# ports.net
KiCad netlist of a schematic drawn in Altium Designer
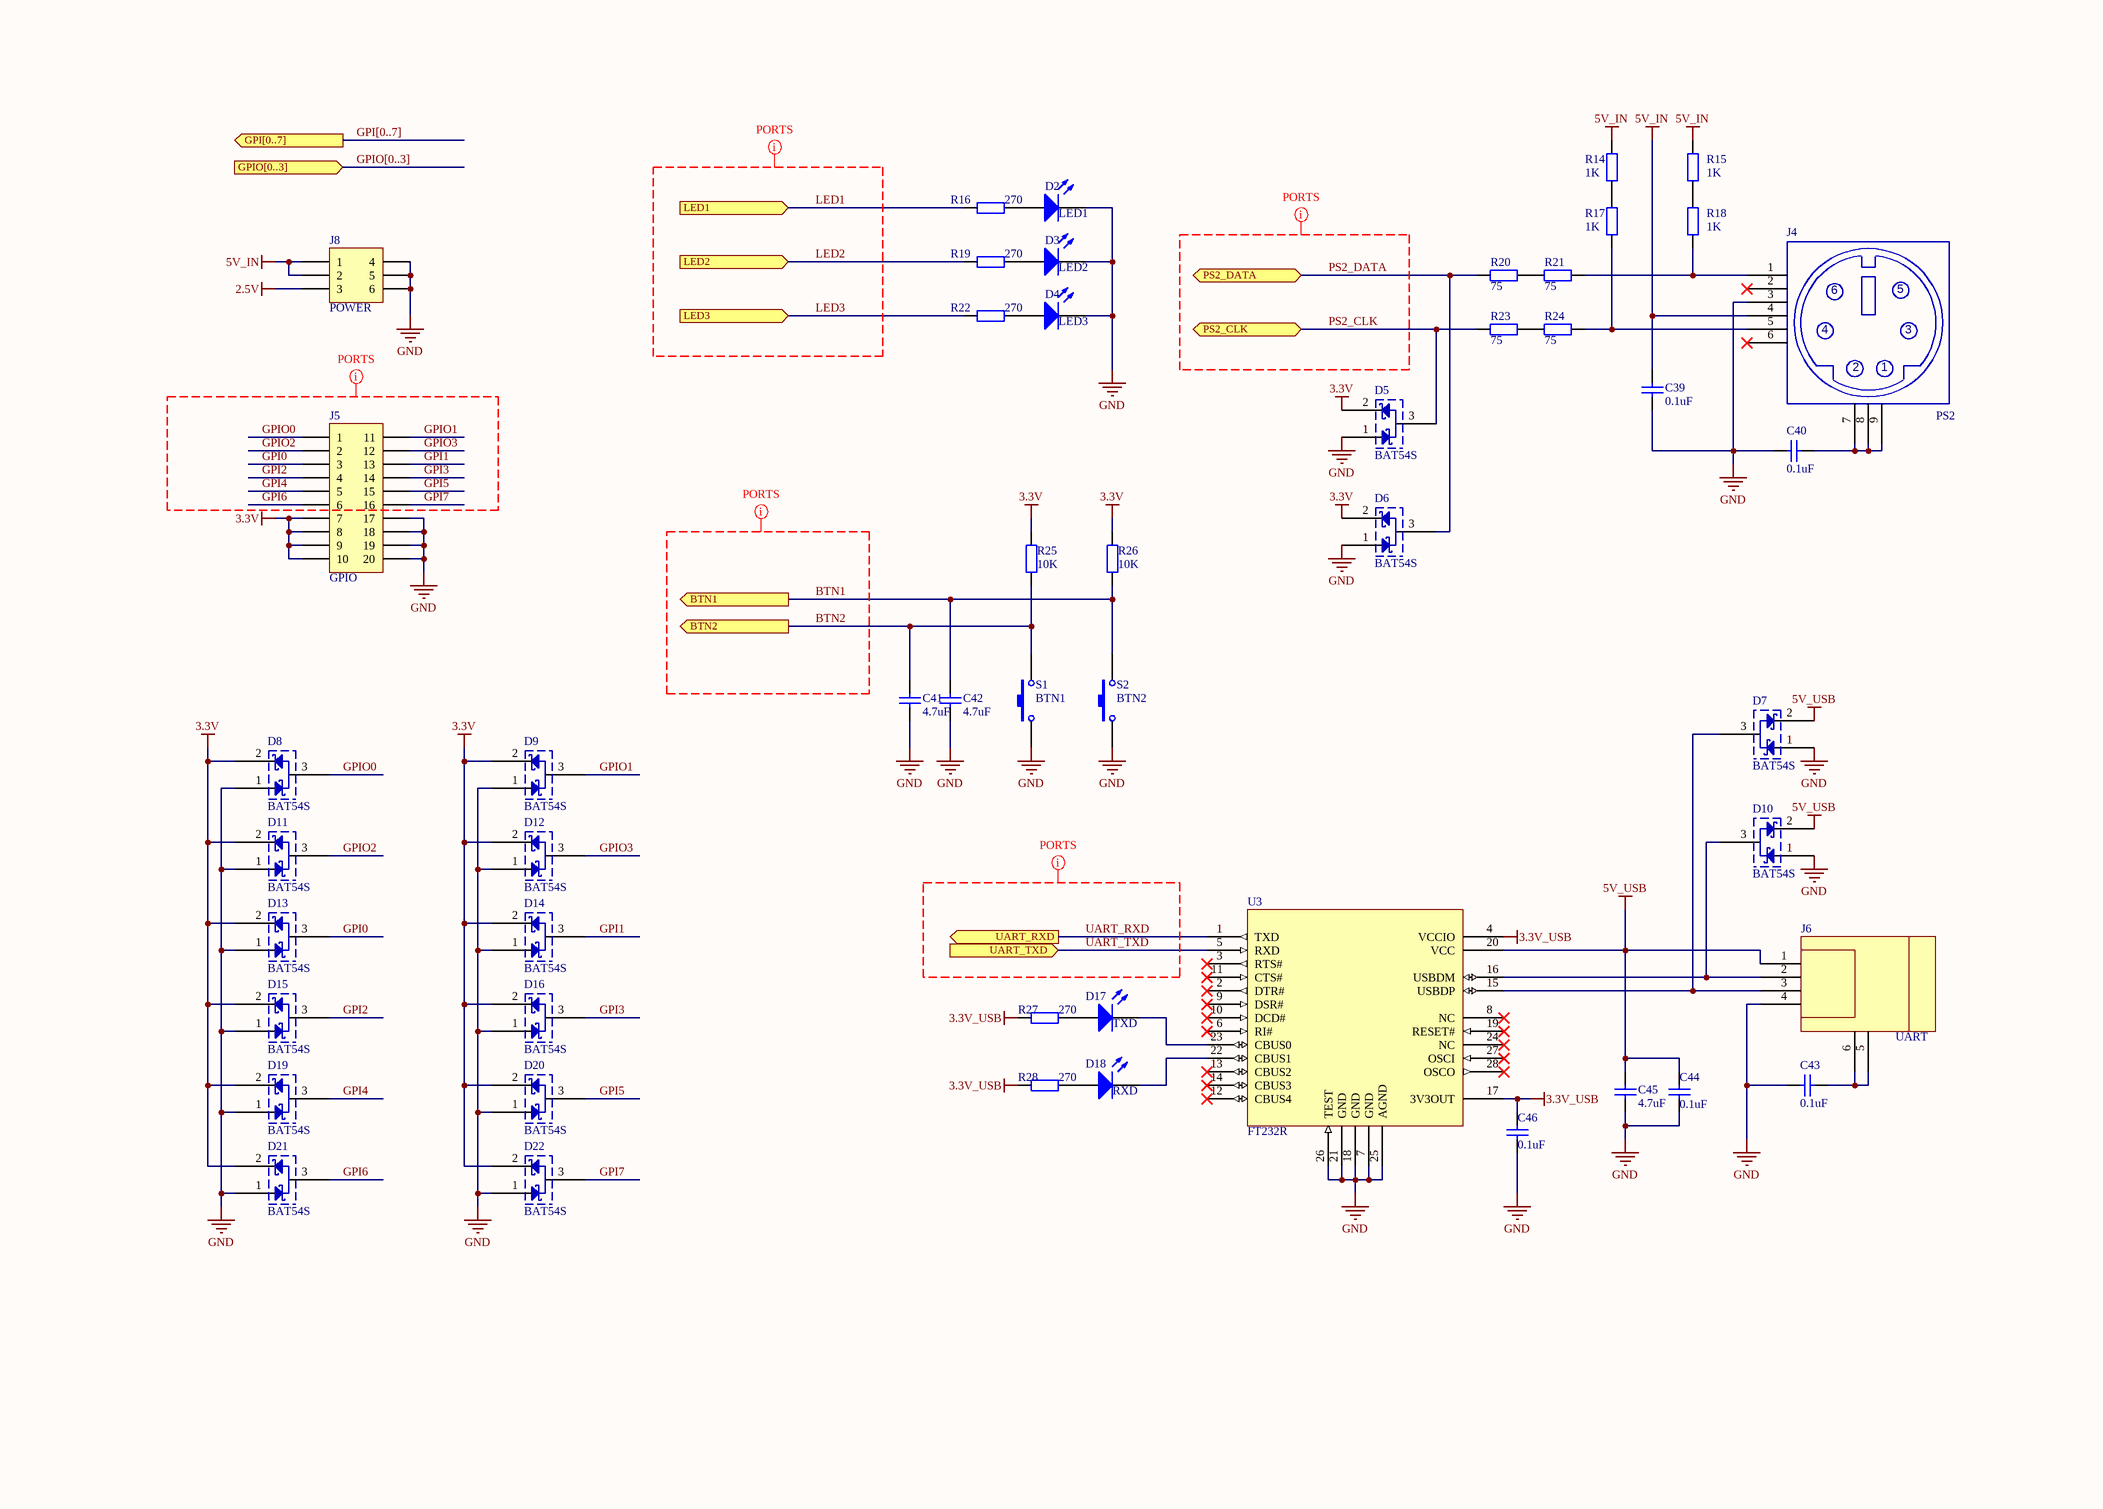
[diagram p0: ports.SchDoc]

(export (version "E")
  (design (tool "Eeschema 10.0.6"))
  (components
    (comp (ref "C39")
      (value "0.1uF")
      (footprint "0402")
      (description "Capacitor")
      (fields (field (name "Comment") "Cap") (field (name "PUBLISHER") "Altium Limited"))
      (libsource (lib "Miscellaneous Devices") (part "Cap"))
    )
    (comp (ref "C40")
      (value "0.1uF")
      (footprint "0402")
      (description "Capacitor")
      (fields (field (name "Comment") "Cap") (field (name "PUBLISHER") "Altium Limited"))
      (libsource (lib "Miscellaneous Devices") (part "Cap"))
    )
    (comp (ref "C41")
      (value "4.7uF")
      (footprint "C0805")
      (description "Capacitor")
      (fields (field (name "Comment") "Cap") (field (name "PUBLISHER") "Altium Limited"))
      (libsource (lib "Miscellaneous Devices") (part "Cap"))
    )
    (comp (ref "C42")
      (value "4.7uF")
      (footprint "C0805")
      (description "Capacitor")
      (fields (field (name "Comment") "Cap") (field (name "PUBLISHER") "Altium Limited"))
      (libsource (lib "Miscellaneous Devices") (part "Cap"))
    )
    (comp (ref "C43")
      (value "0.1uF")
      (footprint "0402")
      (description "Capacitor")
      (fields (field (name "Comment") "Cap") (field (name "PUBLISHER") "Altium Limited"))
      (libsource (lib "Miscellaneous Devices") (part "Cap"))
    )
    (comp (ref "C44")
      (value "0.1uF")
      (footprint "0402")
      (description "Capacitor")
      (fields (field (name "Comment") "Cap") (field (name "PUBLISHER") "Altium Limited"))
      (libsource (lib "Miscellaneous Devices") (part "Cap"))
    )
    (comp (ref "C45")
      (value "4.7uF")
      (footprint "C0805")
      (description "Capacitor")
      (fields (field (name "Comment") "Cap") (field (name "PUBLISHER") "Altium Limited"))
      (libsource (lib "Miscellaneous Devices") (part "Cap"))
    )
    (comp (ref "C46")
      (value "0.1uF")
      (footprint "0402")
      (description "Capacitor")
      (fields (field (name "Comment") "Cap") (field (name "PUBLISHER") "Altium Limited"))
      (libsource (lib "Miscellaneous Devices") (part "Cap"))
    )
    (comp (ref "D2")
      (value "LED1")
      (footprint "LED")
      (description "Amber")
      (fields (field (name "PUBLISHER") "Altium Limited"))
      (libsource (lib "Miscellaneous Devices") (part "LED3"))
    )
    (comp (ref "D3")
      (value "LED2")
      (footprint "LED")
      (description "Amber")
      (fields (field (name "PUBLISHER") "Altium Limited"))
      (libsource (lib "Miscellaneous Devices") (part "LED3"))
    )
    (comp (ref "D4")
      (value "LED3")
      (footprint "LED")
      (description "Amber")
      (fields (field (name "PUBLISHER") "Altium Limited"))
      (libsource (lib "Miscellaneous Devices") (part "LED3"))
    )
    (comp (ref "D5")
      (value "BAT54S")
      (footprint "SOT23_BAT54S")
      (libsource (lib "FPGA_board") (part "BAT54S"))
    )
    (comp (ref "D6")
      (value "BAT54S")
      (footprint "SOT23_BAT54S")
      (libsource (lib "FPGA_board") (part "BAT54S"))
    )
    (comp (ref "D7")
      (value "BAT54S")
      (footprint "SOT23_BAT54S")
      (libsource (lib "FPGA_board") (part "BAT54S"))
    )
    (comp (ref "D8")
      (value "BAT54S")
      (footprint "SOT23_BAT54S")
      (libsource (lib "FPGA_board") (part "BAT54S"))
    )
    (comp (ref "D9")
      (value "BAT54S")
      (footprint "SOT23_BAT54S")
      (libsource (lib "FPGA_board") (part "BAT54S"))
    )
    (comp (ref "D10")
      (value "BAT54S")
      (footprint "SOT23_BAT54S")
      (libsource (lib "FPGA_board") (part "BAT54S"))
    )
    (comp (ref "D11")
      (value "BAT54S")
      (footprint "SOT23_BAT54S")
      (libsource (lib "FPGA_board") (part "BAT54S"))
    )
    (comp (ref "D12")
      (value "BAT54S")
      (footprint "SOT23_BAT54S")
      (libsource (lib "FPGA_board") (part "BAT54S"))
    )
    (comp (ref "D13")
      (value "BAT54S")
      (footprint "SOT23_BAT54S")
      (libsource (lib "FPGA_board") (part "BAT54S"))
    )
    (comp (ref "D14")
      (value "BAT54S")
      (footprint "SOT23_BAT54S")
      (libsource (lib "FPGA_board") (part "BAT54S"))
    )
    (comp (ref "D15")
      (value "BAT54S")
      (footprint "SOT23_BAT54S")
      (libsource (lib "FPGA_board") (part "BAT54S"))
    )
    (comp (ref "D16")
      (value "BAT54S")
      (footprint "SOT23_BAT54S")
      (libsource (lib "FPGA_board") (part "BAT54S"))
    )
    (comp (ref "D17")
      (value "TXD")
      (footprint "LED")
      (description "Green")
      (fields (field (name "PUBLISHER") "Altium Limited"))
      (libsource (lib "Miscellaneous Devices") (part "LED3"))
    )
    (comp (ref "D18")
      (value "RXD")
      (footprint "LED")
      (description "Red")
      (fields (field (name "PUBLISHER") "Altium Limited"))
      (libsource (lib "Miscellaneous Devices") (part "LED3"))
    )
    (comp (ref "D19")
      (value "BAT54S")
      (footprint "SOT23_BAT54S")
      (libsource (lib "FPGA_board") (part "BAT54S"))
    )
    (comp (ref "D20")
      (value "BAT54S")
      (footprint "SOT23_BAT54S")
      (libsource (lib "FPGA_board") (part "BAT54S"))
    )
    (comp (ref "D21")
      (value "BAT54S")
      (footprint "SOT23_BAT54S")
      (libsource (lib "FPGA_board") (part "BAT54S"))
    )
    (comp (ref "D22")
      (value "BAT54S")
      (footprint "SOT23_BAT54S")
      (libsource (lib "FPGA_board") (part "BAT54S"))
    )
    (comp (ref "J4") (value "PS2") (footprint "PS2-6PIN") (libsource (lib "FPGA_board") (part "PS2_Socket")))
    (comp (ref "J5")
      (value "GPIO")
      (footprint "HDR2X10_CEN")
      (description "Header, 10-Pin, Dual row")
      (fields (field (name "PUBLISHER") "Altium Limited"))
      (libsource (lib "Miscellaneous Connectors") (part "Header 10X2A"))
    )
    (comp (ref "J6") (value "UART") (footprint "USB_B") (libsource (lib "FPGA_board") (part "USB_B")))
    (comp (ref "J8")
      (value "POWER")
      (footprint "HDR2X3_CEN")
      (description "Header, 3-Pin, Dual row")
      (fields (field (name "PUBLISHER") "Altium Limited"))
      (libsource (lib "Miscellaneous Connectors") (part "Header 3X2A"))
    )
    (comp (ref "R14")
      (value "1K")
      (footprint "J1-0603")
      (description "Resistor")
      (fields (field (name "Comment") "Res2") (field (name "PUBLISHER") "Altium Limited"))
      (libsource (lib "Miscellaneous Devices") (part "Res2"))
    )
    (comp (ref "R15")
      (value "1K")
      (footprint "J1-0603")
      (description "Resistor")
      (fields (field (name "Comment") "Res2") (field (name "PUBLISHER") "Altium Limited"))
      (libsource (lib "Miscellaneous Devices") (part "Res2"))
    )
    (comp (ref "R16")
      (value "270")
      (footprint "6-0805_N")
      (description "Resistor")
      (fields (field (name "Comment") "Res2") (field (name "PUBLISHER") "Altium Limited"))
      (libsource (lib "") (part "Res2_1"))
    )
    (comp (ref "R17")
      (value "1K")
      (footprint "J1-0603")
      (description "Resistor")
      (fields (field (name "Comment") "Res2") (field (name "PUBLISHER") "Altium Limited"))
      (libsource (lib "Miscellaneous Devices") (part "Res2"))
    )
    (comp (ref "R18")
      (value "1K")
      (footprint "J1-0603")
      (description "Resistor")
      (fields (field (name "Comment") "Res2") (field (name "PUBLISHER") "Altium Limited"))
      (libsource (lib "Miscellaneous Devices") (part "Res2"))
    )
    (comp (ref "R19")
      (value "270")
      (footprint "6-0805_N")
      (description "Resistor")
      (fields (field (name "Comment") "Res2") (field (name "PUBLISHER") "Altium Limited"))
      (libsource (lib "") (part "Res2_1"))
    )
    (comp (ref "R20")
      (value "75")
      (footprint "J1-0603")
      (description "Resistor")
      (fields (field (name "Comment") "Res2") (field (name "PUBLISHER") "Altium Limited"))
      (libsource (lib "") (part "Res2_2"))
    )
    (comp (ref "R21")
      (value "75")
      (footprint "J1-0603")
      (description "Resistor")
      (fields (field (name "Comment") "Res2") (field (name "PUBLISHER") "Altium Limited"))
      (libsource (lib "") (part "Res2_2"))
    )
    (comp (ref "R22")
      (value "270")
      (footprint "6-0805_N")
      (description "Resistor")
      (fields (field (name "Comment") "Res2") (field (name "PUBLISHER") "Altium Limited"))
      (libsource (lib "") (part "Res2_1"))
    )
    (comp (ref "R23")
      (value "75")
      (footprint "J1-0603")
      (description "Resistor")
      (fields (field (name "Comment") "Res2") (field (name "PUBLISHER") "Altium Limited"))
      (libsource (lib "") (part "Res2_2"))
    )
    (comp (ref "R24")
      (value "75")
      (footprint "J1-0603")
      (description "Resistor")
      (fields (field (name "Comment") "Res2") (field (name "PUBLISHER") "Altium Limited"))
      (libsource (lib "") (part "Res2_2"))
    )
    (comp (ref "R25")
      (value "10K")
      (footprint "J1-0603")
      (description "Resistor")
      (fields (field (name "Comment") "Res2") (field (name "PUBLISHER") "Altium Limited"))
      (libsource (lib "") (part "Res2_3"))
    )
    (comp (ref "R26")
      (value "10K")
      (footprint "J1-0603")
      (description "Resistor")
      (fields (field (name "Comment") "Res2") (field (name "PUBLISHER") "Altium Limited"))
      (libsource (lib "") (part "Res2_3"))
    )
    (comp (ref "R27")
      (value "270")
      (footprint "6-0805_N")
      (description "Resistor")
      (fields (field (name "Comment") "Res2") (field (name "PUBLISHER") "Altium Limited"))
      (libsource (lib "") (part "Res2_1"))
    )
    (comp (ref "R28")
      (value "270")
      (footprint "6-0805_N")
      (description "Resistor")
      (fields (field (name "Comment") "Res2") (field (name "PUBLISHER") "Altium Limited"))
      (libsource (lib "") (part "Res2_1"))
    )
    (comp (ref "S1")
      (value "BTN1")
      (footprint "PUSHBUTTON")
      (description "Switch")
      (fields (field (name "PUBLISHER") "Altium Limited"))
      (libsource (lib "Miscellaneous Devices") (part "SW-PB"))
    )
    (comp (ref "S2")
      (value "BTN2")
      (footprint "PUSHBUTTON")
      (description "Switch")
      (fields (field (name "PUBLISHER") "Altium Limited"))
      (libsource (lib "Miscellaneous Devices") (part "SW-PB"))
    )
    (comp (ref "U3") (value "FT232R") (footprint "SSOP28") (libsource (lib "FPGA_board") (part "FT232R")))
  )
  (nets
    (net (code "1") (name "/BTN1") (class "Default")
      (node (ref "C42") (pin "2") (pinfunction "2_2") (pintype "passive"))
      (node (ref "R26") (pin "2") (pinfunction "2_2") (pintype "passive"))
      (node (ref "S2") (pin "2") (pinfunction "2_2") (pintype "passive"))
    )
    (net (code "2") (name "/BTN2") (class "Default")
      (node (ref "C41") (pin "2") (pinfunction "2_2") (pintype "passive"))
      (node (ref "R25") (pin "2") (pinfunction "2_2") (pintype "passive"))
      (node (ref "S1") (pin "2") (pinfunction "2_2") (pintype "passive"))
    )
    (net (code "3") (name "/GPI0") (class "Default")
      (node (ref "D13") (pin "3") (pinfunction "3_3") (pintype "passive"))
      (node (ref "J5") (pin "3") (pinfunction "3_3") (pintype "passive"))
    )
    (net (code "4") (name "/GPI1") (class "Default")
      (node (ref "D14") (pin "3") (pinfunction "3_3") (pintype "passive"))
      (node (ref "J5") (pin "13") (pinfunction "13_13") (pintype "passive"))
    )
    (net (code "5") (name "/GPI2") (class "Default")
      (node (ref "D15") (pin "3") (pinfunction "3_3") (pintype "passive"))
      (node (ref "J5") (pin "4") (pinfunction "4_4") (pintype "passive"))
    )
    (net (code "6") (name "/GPI3") (class "Default")
      (node (ref "D16") (pin "3") (pinfunction "3_3") (pintype "passive"))
      (node (ref "J5") (pin "14") (pinfunction "14_14") (pintype "passive"))
    )
    (net (code "7") (name "/GPI4") (class "Default")
      (node (ref "D19") (pin "3") (pinfunction "3_3") (pintype "passive"))
      (node (ref "J5") (pin "5") (pinfunction "5_5") (pintype "passive"))
    )
    (net (code "8") (name "/GPI5") (class "Default")
      (node (ref "D20") (pin "3") (pinfunction "3_3") (pintype "passive"))
      (node (ref "J5") (pin "15") (pinfunction "15_15") (pintype "passive"))
    )
    (net (code "9") (name "/GPI6") (class "Default")
      (node (ref "D21") (pin "3") (pinfunction "3_3") (pintype "passive"))
      (node (ref "J5") (pin "6") (pinfunction "6_6") (pintype "passive"))
    )
    (net (code "10") (name "/GPI7") (class "Default")
      (node (ref "D22") (pin "3") (pinfunction "3_3") (pintype "passive"))
      (node (ref "J5") (pin "16") (pinfunction "16_16") (pintype "passive"))
    )
    (net (code "11") (name "/GPIO0") (class "Default")
      (node (ref "D8") (pin "3") (pinfunction "3_3") (pintype "passive"))
      (node (ref "J5") (pin "1") (pinfunction "1_1") (pintype "passive"))
    )
    (net (code "12") (name "/GPIO1") (class "Default")
      (node (ref "D9") (pin "3") (pinfunction "3_3") (pintype "passive"))
      (node (ref "J5") (pin "11") (pinfunction "11_11") (pintype "passive"))
    )
    (net (code "13") (name "/GPIO2") (class "Default")
      (node (ref "D11") (pin "3") (pinfunction "3_3") (pintype "passive"))
      (node (ref "J5") (pin "2") (pinfunction "2_2") (pintype "passive"))
    )
    (net (code "14") (name "/GPIO3") (class "Default")
      (node (ref "D12") (pin "3") (pinfunction "3_3") (pintype "passive"))
      (node (ref "J5") (pin "12") (pinfunction "12_12") (pintype "passive"))
    )
    (net (code "17") (name "/LED1") (class "Default")
      (node (ref "R16") (pin "2") (pinfunction "2_2") (pintype "passive"))
    )
    (net (code "18") (name "/LED2") (class "Default")
      (node (ref "R19") (pin "2") (pinfunction "2_2") (pintype "passive"))
    )
    (net (code "19") (name "/LED3") (class "Default")
      (node (ref "R22") (pin "2") (pinfunction "2_2") (pintype "passive"))
    )
    (net (code "20") (name "/PS2_CLK") (class "Default")
      (node (ref "D5") (pin "3") (pinfunction "3_3") (pintype "passive"))
      (node (ref "R23") (pin "1") (pinfunction "1_1") (pintype "passive"))
    )
    (net (code "21") (name "/PS2_DATA") (class "Default")
      (node (ref "D6") (pin "3") (pinfunction "3_3") (pintype "passive"))
      (node (ref "R20") (pin "1") (pinfunction "1_1") (pintype "passive"))
    )
    (net (code "22") (name "/UART_RXD") (class "Default")
      (node (ref "U3") (pin "1") (pinfunction "TXD_1") (pintype "output"))
    )
    (net (code "23") (name "/UART_TXD") (class "Default")
      (node (ref "U3") (pin "5") (pinfunction "RXD_5") (pintype "input"))
    )
    (net (code "24") (name "2.5V") (class "Default")
      (node (ref "J8") (pin "3") (pinfunction "3_3") (pintype "passive"))
    )
    (net (code "25") (name "3.3V") (class "Default")
      (node (ref "D11") (pin "2") (pinfunction "2_2") (pintype "passive"))
      (node (ref "D12") (pin "2") (pinfunction "2_2") (pintype "passive"))
      (node (ref "D13") (pin "2") (pinfunction "2_2") (pintype "passive"))
      (node (ref "D14") (pin "2") (pinfunction "2_2") (pintype "passive"))
      (node (ref "D15") (pin "2") (pinfunction "2_2") (pintype "passive"))
      (node (ref "D16") (pin "2") (pinfunction "2_2") (pintype "passive"))
      (node (ref "D19") (pin "2") (pinfunction "2_2") (pintype "passive"))
      (node (ref "D20") (pin "2") (pinfunction "2_2") (pintype "passive"))
      (node (ref "D21") (pin "2") (pinfunction "2_2") (pintype "passive"))
      (node (ref "D22") (pin "2") (pinfunction "2_2") (pintype "passive"))
      (node (ref "D5") (pin "2") (pinfunction "2_2") (pintype "passive"))
      (node (ref "D6") (pin "2") (pinfunction "2_2") (pintype "passive"))
      (node (ref "D8") (pin "2") (pinfunction "2_2") (pintype "passive"))
      (node (ref "D9") (pin "2") (pinfunction "2_2") (pintype "passive"))
      (node (ref "J5") (pin "10") (pinfunction "10_10") (pintype "passive"))
      (node (ref "J5") (pin "7") (pinfunction "7_7") (pintype "passive"))
      (node (ref "J5") (pin "8") (pinfunction "8_8") (pintype "passive"))
      (node (ref "J5") (pin "9") (pinfunction "9_9") (pintype "passive"))
      (node (ref "R25") (pin "1") (pinfunction "1_1") (pintype "passive"))
      (node (ref "R26") (pin "1") (pinfunction "1_1") (pintype "passive"))
    )
    (net (code "26") (name "3.3V_USB") (class "Default")
      (node (ref "C46") (pin "1") (pinfunction "1_1") (pintype "passive"))
      (node (ref "R27") (pin "2") (pinfunction "2_2") (pintype "passive"))
      (node (ref "R28") (pin "2") (pinfunction "2_2") (pintype "passive"))
      (node (ref "U3") (pin "17") (pinfunction "3V3OUT_17") (pintype "power_in"))
      (node (ref "U3") (pin "4") (pinfunction "VCCIO_4") (pintype "power_in"))
    )
    (net (code "27") (name "5V_IN") (class "Default")
      (node (ref "C39") (pin "2") (pinfunction "2_2") (pintype "passive"))
      (node (ref "J4") (pin "4") (pintype "passive"))
      (node (ref "J8") (pin "1") (pinfunction "1_1") (pintype "passive"))
      (node (ref "J8") (pin "2") (pinfunction "2_2") (pintype "passive"))
      (node (ref "R14") (pin "2") (pinfunction "2_2") (pintype "passive"))
      (node (ref "R15") (pin "2") (pinfunction "2_2") (pintype "passive"))
    )
    (net (code "28") (name "5V_USB") (class "Default")
      (node (ref "C44") (pin "1") (pinfunction "1_1") (pintype "passive"))
      (node (ref "C45") (pin "2") (pinfunction "2_2") (pintype "passive"))
      (node (ref "D10") (pin "2") (pinfunction "2_2") (pintype "passive"))
      (node (ref "D7") (pin "2") (pinfunction "2_2") (pintype "passive"))
      (node (ref "J6") (pin "1") (pintype "passive"))
      (node (ref "U3") (pin "20") (pinfunction "VCC_20") (pintype "power_in"))
    )
    (net (code "29") (name "GND") (class "Default")
      (node (ref "C39") (pin "1") (pinfunction "1_1") (pintype "passive"))
      (node (ref "C40") (pin "1") (pinfunction "1_1") (pintype "passive"))
      (node (ref "C41") (pin "1") (pinfunction "1_1") (pintype "passive"))
      (node (ref "C42") (pin "1") (pinfunction "1_1") (pintype "passive"))
      (node (ref "C43") (pin "1") (pinfunction "1_1") (pintype "passive"))
      (node (ref "C44") (pin "2") (pinfunction "2_2") (pintype "passive"))
      (node (ref "C45") (pin "1") (pinfunction "1_1") (pintype "passive"))
      (node (ref "C46") (pin "2") (pinfunction "2_2") (pintype "passive"))
      (node (ref "D10") (pin "1") (pinfunction "1_1") (pintype "passive"))
      (node (ref "D11") (pin "1") (pinfunction "1_1") (pintype "passive"))
      (node (ref "D12") (pin "1") (pinfunction "1_1") (pintype "passive"))
      (node (ref "D13") (pin "1") (pinfunction "1_1") (pintype "passive"))
      (node (ref "D14") (pin "1") (pinfunction "1_1") (pintype "passive"))
      (node (ref "D15") (pin "1") (pinfunction "1_1") (pintype "passive"))
      (node (ref "D16") (pin "1") (pinfunction "1_1") (pintype "passive"))
      (node (ref "D19") (pin "1") (pinfunction "1_1") (pintype "passive"))
      (node (ref "D2") (pin "2") (pinfunction "K_2") (pintype "passive"))
      (node (ref "D20") (pin "1") (pinfunction "1_1") (pintype "passive"))
      (node (ref "D21") (pin "1") (pinfunction "1_1") (pintype "passive"))
      (node (ref "D22") (pin "1") (pinfunction "1_1") (pintype "passive"))
      (node (ref "D3") (pin "2") (pinfunction "K_2") (pintype "passive"))
      (node (ref "D4") (pin "2") (pinfunction "K_2") (pintype "passive"))
      (node (ref "D5") (pin "1") (pinfunction "1_1") (pintype "passive"))
      (node (ref "D6") (pin "1") (pinfunction "1_1") (pintype "passive"))
      (node (ref "D7") (pin "1") (pinfunction "1_1") (pintype "passive"))
      (node (ref "D8") (pin "1") (pinfunction "1_1") (pintype "passive"))
      (node (ref "D9") (pin "1") (pinfunction "1_1") (pintype "passive"))
      (node (ref "J4") (pin "3") (pintype "passive"))
      (node (ref "J5") (pin "17") (pinfunction "17_17") (pintype "passive"))
      (node (ref "J5") (pin "18") (pinfunction "18_18") (pintype "passive"))
      (node (ref "J5") (pin "19") (pinfunction "19_19") (pintype "passive"))
      (node (ref "J5") (pin "20") (pinfunction "20_20") (pintype "passive"))
      (node (ref "J6") (pin "4") (pintype "passive"))
      (node (ref "J8") (pin "4") (pinfunction "4_4") (pintype "passive"))
      (node (ref "J8") (pin "5") (pinfunction "5_5") (pintype "passive"))
      (node (ref "J8") (pin "6") (pinfunction "6_6") (pintype "passive"))
      (node (ref "S1") (pin "1") (pinfunction "1_1") (pintype "passive"))
      (node (ref "S2") (pin "1") (pinfunction "1_1") (pintype "passive"))
      (node (ref "U3") (pin "18") (pinfunction "GND_18") (pintype "power_in"))
      (node (ref "U3") (pin "21") (pinfunction "GND_21") (pintype "power_in"))
      (node (ref "U3") (pin "25") (pinfunction "AGND_25") (pintype "power_in"))
      (node (ref "U3") (pin "26") (pinfunction "TEST_26") (pintype "input"))
      (node (ref "U3") (pin "7") (pinfunction "GND_7") (pintype "power_in"))
    )
    (net (code "30") (name "Net-(C40-Pad2)") (class "Default")
      (node (ref "C40") (pin "2") (pinfunction "2_2") (pintype "passive"))
      (node (ref "J4") (pin "7") (pintype "passive"))
      (node (ref "J4") (pin "8") (pintype "passive"))
      (node (ref "J4") (pin "9") (pintype "passive"))
    )
    (net (code "31") (name "Net-(C43-Pad2)") (class "Default")
      (node (ref "C43") (pin "2") (pinfunction "2_2") (pintype "passive"))
      (node (ref "J6") (pin "5") (pintype "passive"))
      (node (ref "J6") (pin "6") (pintype "passive"))
    )
    (net (code "32") (name "Net-(D2-A)") (class "Default")
      (node (ref "D2") (pin "1") (pinfunction "A_1") (pintype "passive"))
      (node (ref "R16") (pin "1") (pinfunction "1_1") (pintype "passive"))
    )
    (net (code "33") (name "Net-(D3-A)") (class "Default")
      (node (ref "D3") (pin "1") (pinfunction "A_1") (pintype "passive"))
      (node (ref "R19") (pin "1") (pinfunction "1_1") (pintype "passive"))
    )
    (net (code "34") (name "Net-(D4-A)") (class "Default")
      (node (ref "D4") (pin "1") (pinfunction "A_1") (pintype "passive"))
      (node (ref "R22") (pin "1") (pinfunction "1_1") (pintype "passive"))
    )
    (net (code "35") (name "Net-(D17-A)") (class "Default")
      (node (ref "D17") (pin "1") (pinfunction "A_1") (pintype "passive"))
      (node (ref "R27") (pin "1") (pinfunction "1_1") (pintype "passive"))
    )
    (net (code "36") (name "Net-(D17-K)") (class "Default")
      (node (ref "D17") (pin "2") (pinfunction "K_2") (pintype "passive"))
      (node (ref "U3") (pin "23") (pinfunction "CBUS0_23") (pintype "bidirectional"))
    )
    (net (code "37") (name "Net-(D18-A)") (class "Default")
      (node (ref "D18") (pin "1") (pinfunction "A_1") (pintype "passive"))
      (node (ref "R28") (pin "1") (pinfunction "1_1") (pintype "passive"))
    )
    (net (code "38") (name "Net-(D18-K)") (class "Default")
      (node (ref "D18") (pin "2") (pinfunction "K_2") (pintype "passive"))
      (node (ref "U3") (pin "22") (pinfunction "CBUS1_22") (pintype "bidirectional"))
    )
    (net (code "39") (name "Net-(J4-Pad1)") (class "Default")
      (node (ref "J4") (pin "1") (pintype "passive"))
      (node (ref "R18") (pin "1") (pinfunction "1_1") (pintype "passive"))
      (node (ref "R21") (pin "2") (pinfunction "2_2") (pintype "passive"))
    )
    (net (code "40") (name "Net-(J4-Pad5)") (class "Default")
      (node (ref "J4") (pin "5") (pintype "passive"))
      (node (ref "R17") (pin "1") (pinfunction "1_1") (pintype "passive"))
      (node (ref "R24") (pin "2") (pinfunction "2_2") (pintype "passive"))
    )
    (net (code "41") (name "Net-(R14-Pad1)") (class "Default")
      (node (ref "R14") (pin "1") (pinfunction "1_1") (pintype "passive"))
      (node (ref "R17") (pin "2") (pinfunction "2_2") (pintype "passive"))
    )
    (net (code "42") (name "Net-(R15-Pad1)") (class "Default")
      (node (ref "R15") (pin "1") (pinfunction "1_1") (pintype "passive"))
      (node (ref "R18") (pin "2") (pinfunction "2_2") (pintype "passive"))
    )
    (net (code "43") (name "Net-(R20-Pad2)") (class "Default")
      (node (ref "R20") (pin "2") (pinfunction "2_2") (pintype "passive"))
      (node (ref "R21") (pin "1") (pinfunction "1_1") (pintype "passive"))
    )
    (net (code "44") (name "Net-(R23-Pad2)") (class "Default")
      (node (ref "R23") (pin "2") (pinfunction "2_2") (pintype "passive"))
      (node (ref "R24") (pin "1") (pinfunction "1_1") (pintype "passive"))
    )
    (net (code "45") (name "Net-(U3-USBDM)") (class "Default")
      (node (ref "D10") (pin "3") (pinfunction "3_3") (pintype "passive"))
      (node (ref "J6") (pin "2") (pintype "passive"))
      (node (ref "U3") (pin "16") (pinfunction "USBDM_16") (pintype "bidirectional"))
    )
    (net (code "46") (name "Net-(U3-USBDP)") (class "Default")
      (node (ref "D7") (pin "3") (pinfunction "3_3") (pintype "passive"))
      (node (ref "J6") (pin "3") (pintype "passive"))
      (node (ref "U3") (pin "15") (pinfunction "USBDP_15") (pintype "bidirectional"))
    )
    (net (code "47") (name "unconnected-(J4-Pad2)") (class "Default")
      (node (ref "J4") (pin "2") (pintype "passive+no_connect"))
    )
    (net (code "48") (name "unconnected-(J4-Pad6)") (class "Default")
      (node (ref "J4") (pin "6") (pintype "passive+no_connect"))
    )
    (net (code "49") (name "unconnected-(U3-CBUS2-Pad13)") (class "Default")
      (node (ref "U3") (pin "13") (pinfunction "CBUS2_13") (pintype "bidirectional+no_connect"))
    )
    (net (code "50") (name "unconnected-(U3-CBUS3-Pad14)") (class "Default")
      (node (ref "U3") (pin "14") (pinfunction "CBUS3_14") (pintype "bidirectional+no_connect"))
    )
    (net (code "51") (name "unconnected-(U3-CBUS4-Pad12)") (class "Default")
      (node (ref "U3") (pin "12") (pinfunction "CBUS4_12") (pintype "bidirectional+no_connect"))
    )
    (net (code "52") (name "unconnected-(U3-CTS#-Pad11)") (class "Default")
      (node (ref "U3") (pin "11") (pinfunction "CTS#_11") (pintype "input+no_connect"))
    )
    (net (code "53") (name "unconnected-(U3-DCD#-Pad10)") (class "Default")
      (node (ref "U3") (pin "10") (pinfunction "DCD#_10") (pintype "input+no_connect"))
    )
    (net (code "54") (name "unconnected-(U3-DSR#-Pad9)") (class "Default")
      (node (ref "U3") (pin "9") (pinfunction "DSR#_9") (pintype "input+no_connect"))
    )
    (net (code "55") (name "unconnected-(U3-DTR#-Pad2)") (class "Default")
      (node (ref "U3") (pin "2") (pinfunction "DTR#_2") (pintype "output+no_connect"))
    )
    (net (code "56") (name "unconnected-(U3-NC-Pad8)") (class "Default")
      (node (ref "U3") (pin "8") (pinfunction "NC_8") (pintype "passive+no_connect"))
    )
    (net (code "57") (name "unconnected-(U3-NC-Pad24)") (class "Default")
      (node (ref "U3") (pin "24") (pinfunction "NC_24") (pintype "passive+no_connect"))
    )
    (net (code "58") (name "unconnected-(U3-OSCI-Pad27)") (class "Default")
      (node (ref "U3") (pin "27") (pinfunction "OSCI_27") (pintype "input+no_connect"))
    )
    (net (code "59") (name "unconnected-(U3-OSCO-Pad28)") (class "Default")
      (node (ref "U3") (pin "28") (pinfunction "OSCO_28") (pintype "output+no_connect"))
    )
    (net (code "60") (name "unconnected-(U3-RESET#-Pad19)") (class "Default")
      (node (ref "U3") (pin "19") (pinfunction "RESET#_19") (pintype "input+no_connect"))
    )
    (net (code "61") (name "unconnected-(U3-RI#-Pad6)") (class "Default")
      (node (ref "U3") (pin "6") (pinfunction "RI#_6") (pintype "input+no_connect"))
    )
    (net (code "62") (name "unconnected-(U3-RTS#-Pad3)") (class "Default")
      (node (ref "U3") (pin "3") (pinfunction "RTS#_3") (pintype "output+no_connect"))
    )
  )
)
